# RX-FM-Super-Regenerative-Tuner-ForcedQue.net
KiCad netlist of a schematic drawn in EAGLE
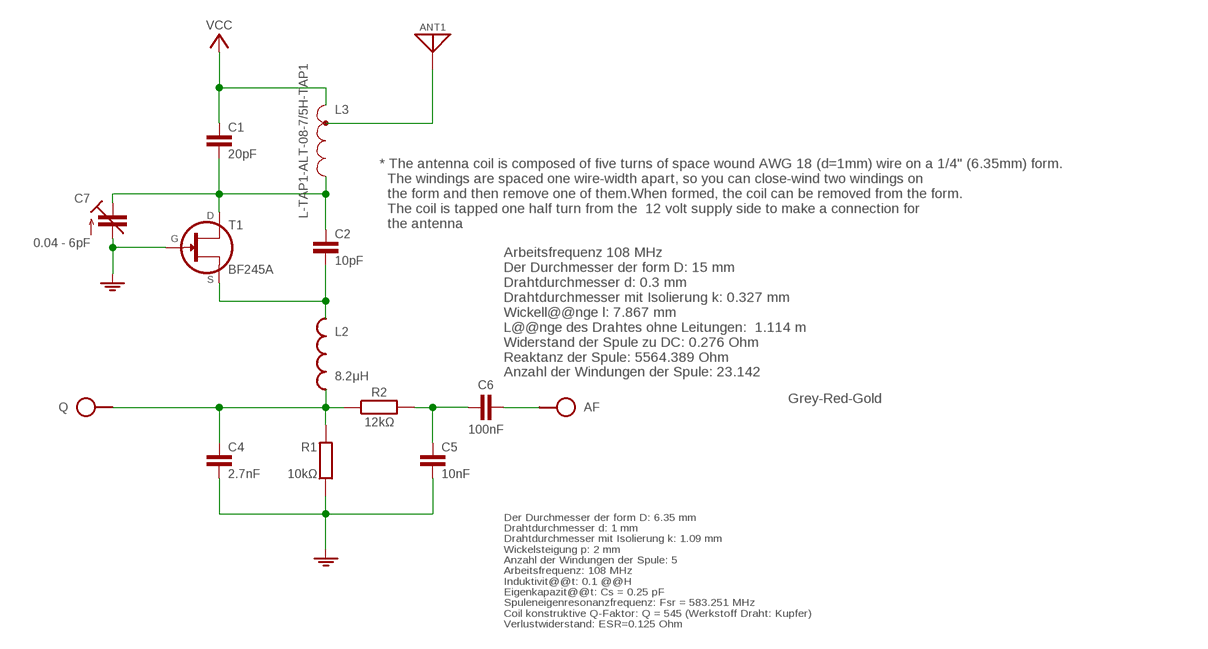
[diagram p0: schematic, sheet 1]

(export (version "E")
  (design (tool "Eeschema 10.0.6"))
  (components
    (comp (ref "AF")
      (value "SPAD")
      (footprint "eagle-import:SPAD")
      (libsource (lib "eagle-import") (part "SPAD"))
    )
    (comp (ref "ANT1")
      (value "ANT")
      (footprint "eagle-import:SPAD")
      (libsource (lib "eagle-import") (part "ANT"))
    )
    (comp (ref "C1")
      (value "20pF")
      (footprint "eagle-import:C025-015X024")
      (libsource (lib "eagle-import") (part "C025-015X024"))
    )
    (comp (ref "C2")
      (value "10pF")
      (footprint "eagle-import:C025-015X024")
      (libsource (lib "eagle-import") (part "C025-015X024"))
    )
    (comp (ref "C4")
      (value "2.7nF")
      (footprint "eagle-import:C050-020X044")
      (libsource (lib "eagle-import") (part "C050-020X044"))
    )
    (comp (ref "C5")
      (value "10nF")
      (footprint "eagle-import:C025-015X024")
      (libsource (lib "eagle-import") (part "C025-015X024"))
    )
    (comp (ref "C6")
      (value "100nF")
      (footprint "eagle-import:C050-020X044")
      (libsource (lib "eagle-import") (part "C-H050-020X044"))
    )
    (comp (ref "C7")
      (value "0.04 - 6pF")
      (footprint "eagle-import:CTRIMTZ03")
      (libsource (lib "eagle-import") (part "C-TR-PH20127-TZ03"))
    )
    (comp (ref "L2")
      (value "8.2μH")
      (footprint "eagle-import:L-04_7-V")
      (libsource (lib "eagle-import") (part "L-ALT-04/7-V"))
    )
    (comp (ref "L3")
      (value "L-TAP1-ALT-08-7/5H-TAP1")
      (footprint "eagle-import:L-08-7_5H-TAP1")
      (libsource (lib "eagle-import") (part "L-TAP1-ALT-08-7/5H-TAP1"))
    )
    (comp (ref "Q")
      (value "SPAD")
      (footprint "eagle-import:SPAD")
      (libsource (lib "eagle-import") (part "SPAD"))
    )
    (comp (ref "R1")
      (value "10kΩ")
      (footprint "eagle-import:0204_7")
      (libsource (lib "eagle-import") (part "R0204/7"))
    )
    (comp (ref "R2")
      (value "12kΩ")
      (footprint "eagle-import:0204_7")
      (libsource (lib "eagle-import") (part "R-H0204/7"))
    )
    (comp (ref "S1")
      (value "VCC_GNDPWR-L")
      (footprint "eagle-import:PWR-L")
      (libsource (lib "eagle-import") (part "VCC_GNDPWR-L"))
    )
    (comp (ref "T1")
      (value "BF245A")
      (footprint "eagle-import:TO92-GSD")
      (libsource (lib "eagle-import") (part "BF245BTO92"))
    )
  )
  (nets
    (net (code "1") (name "GND") (class "Default")
      (node (ref "C4") (pin "2") (pinfunction "2_2") (pintype "passive"))
      (node (ref "C5") (pin "2") (pinfunction "2_2") (pintype "passive"))
      (node (ref "C7") (pin "1") (pinfunction "A_1") (pintype "passive"))
      (node (ref "R1") (pin "1") (pinfunction "2_1") (pintype "passive"))
      (node (ref "S1") (pin "1") (pinfunction "GND_1") (pintype "power_in"))
      (node (ref "T1") (pin "1") (pinfunction "G_1") (pintype "passive"))
    )
    (net (code "2") (name "Net-(AF-P$1)") (class "Default")
      (node (ref "AF") (pin "1") (pinfunction "P$1_1") (pintype "passive"))
      (node (ref "C6") (pin "2") (pinfunction "2_2") (pintype "passive"))
    )
    (net (code "3") (name "Net-(C5-Pad1)") (class "Default")
      (node (ref "C5") (pin "1") (pinfunction "1_1") (pintype "passive"))
      (node (ref "C6") (pin "1") (pinfunction "1_1") (pintype "passive"))
      (node (ref "R2") (pin "2") (pinfunction "2_2") (pintype "passive"))
    )
    (net (code "4") (name "Net-(C7-E)") (class "Default")
      (node (ref "C1") (pin "2") (pinfunction "2_2") (pintype "passive"))
      (node (ref "C2") (pin "1") (pinfunction "1_1") (pintype "passive"))
      (node (ref "C7") (pin "2") (pinfunction "E_2") (pintype "passive"))
      (node (ref "L3") (pin "2") (pinfunction "2_2") (pintype "passive"))
      (node (ref "T1") (pin "3") (pinfunction "D_3") (pintype "passive"))
    )
    (net (code "5") (name "Net-(L3-T)") (class "Default")
      (node (ref "ANT1") (pin "1") (pinfunction "1_1") (pintype "output"))
      (node (ref "L3") (pin "3") (pinfunction "T_3") (pintype "passive"))
    )
    (net (code "6") (name "Net-(Q-P$1)") (class "Default")
      (node (ref "C4") (pin "1") (pinfunction "1_1") (pintype "passive"))
      (node (ref "L2") (pin "2") (pinfunction "2_2") (pintype "passive"))
      (node (ref "Q") (pin "1") (pinfunction "P$1_1") (pintype "passive"))
      (node (ref "R1") (pin "2") (pinfunction "1_2") (pintype "passive"))
      (node (ref "R2") (pin "1") (pinfunction "1_1") (pintype "passive"))
    )
    (net (code "7") (name "Net-(S1A-VCC)") (class "Default")
      (node (ref "C1") (pin "1") (pinfunction "1_1") (pintype "passive"))
      (node (ref "L3") (pin "1") (pinfunction "1_1") (pintype "passive"))
      (node (ref "S1") (pin "2") (pinfunction "VCC_2") (pintype "power_in"))
    )
    (net (code "8") (name "Net-(T1-S)") (class "Default")
      (node (ref "C2") (pin "2") (pinfunction "2_2") (pintype "passive"))
      (node (ref "L2") (pin "1") (pinfunction "1_1") (pintype "passive"))
      (node (ref "T1") (pin "2") (pinfunction "S_2") (pintype "passive"))
    )
  )
)
